# main.net
KiCad netlist of a schematic drawn in EAGLE
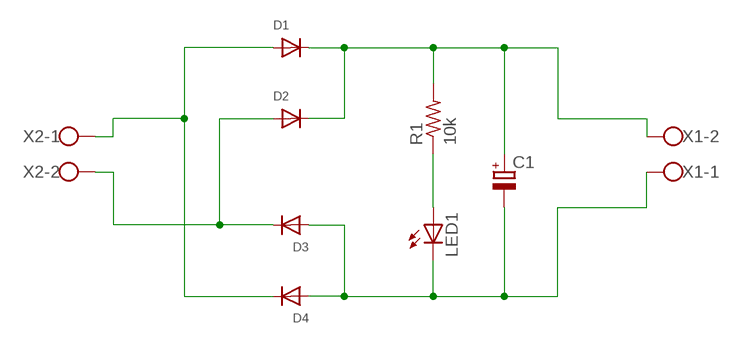
[diagram p0: schematic, sheet 1]

(export (version "E")
  (design (tool "Eeschema 10.0.6"))
  (components
    (comp (ref "C1")
      (value "C-POL_RADIAL-25MM-DIA")
      (footprint "eagle-import:CAPPRD550W110D1250H2500B")
      (libsource (lib "eagle-import") (part "C-POLRADIAL-25MM-DIA_"))
    )
    (comp (ref "D1")
      (value "DIODEDO-1N4148")
      (footprint "eagle-import:DO-1N4148")
      (libsource (lib "eagle-import") (part "DIODEDO-1N4148"))
    )
    (comp (ref "D2")
      (value "DIODEDO-1N4148")
      (footprint "eagle-import:DO-1N4148")
      (libsource (lib "eagle-import") (part "DIODEDO-1N4148"))
    )
    (comp (ref "D3")
      (value "DIODEDO-1N4148")
      (footprint "eagle-import:DO-1N4148")
      (libsource (lib "eagle-import") (part "DIODEDO-1N4148"))
    )
    (comp (ref "D4")
      (value "DIODEDO-1N4148")
      (footprint "eagle-import:DO-1N4148")
      (libsource (lib "eagle-import") (part "DIODEDO-1N4148"))
    )
    (comp (ref "LED1")
      (value "LED5MM")
      (footprint "eagle-import:LED5MM")
      (libsource (lib "eagle-import") (part "LED5MM"))
    )
    (comp (ref "R1")
      (value "10k")
      (footprint "eagle-import:0204_7")
      (libsource (lib "eagle-import") (part "R-US_0204/7"))
    )
    (comp (ref "X1")
      (value "W237-102")
      (footprint "eagle-import:W237-102")
      (fields (field (name "MPN") "237-102"))
      (libsource (lib "eagle-import") (part "W237-102"))
    )
    (comp (ref "X2")
      (value "W237-102")
      (footprint "eagle-import:W237-102")
      (fields (field (name "MPN") "237-102"))
      (libsource (lib "eagle-import") (part "W237-102"))
    )
  )
  (nets
    (net (code "1") (name "Net-(C1-+)") (class "Default")
      (node (ref "C1") (pin "1") (pinfunction "+_1") (pintype "passive"))
      (node (ref "D1") (pin "C") (pinfunction "C_C") (pintype "passive"))
      (node (ref "D2") (pin "C") (pinfunction "C_C") (pintype "passive"))
      (node (ref "R1") (pin "2") (pinfunction "2_2") (pintype "passive"))
      (node (ref "X1") (pin "2") (pinfunction "KL_2") (pintype "passive"))
    )
    (net (code "2") (name "Net-(C1--)") (class "Default")
      (node (ref "C1") (pin "2") (pinfunction "-_2") (pintype "passive"))
      (node (ref "D3") (pin "A") (pinfunction "A_A") (pintype "passive"))
      (node (ref "D4") (pin "A") (pinfunction "A_A") (pintype "passive"))
      (node (ref "LED1") (pin "K") (pinfunction "C_K") (pintype "passive"))
      (node (ref "X1") (pin "1") (pinfunction "KL_1") (pintype "passive"))
    )
    (net (code "3") (name "Net-(LED1-PadA)") (class "Default")
      (node (ref "LED1") (pin "A") (pinfunction "A_A") (pintype "passive"))
      (node (ref "R1") (pin "1") (pinfunction "1_1") (pintype "passive"))
    )
    (net (code "4") (name "Net-(X2A-KL)") (class "Default")
      (node (ref "D1") (pin "A") (pinfunction "A_A") (pintype "passive"))
      (node (ref "D4") (pin "C") (pinfunction "C_C") (pintype "passive"))
      (node (ref "X2") (pin "1") (pinfunction "KL_1") (pintype "passive"))
    )
    (net (code "5") (name "Net-(X2B-KL)") (class "Default")
      (node (ref "D2") (pin "A") (pinfunction "A_A") (pintype "passive"))
      (node (ref "D3") (pin "C") (pinfunction "C_C") (pintype "passive"))
      (node (ref "X2") (pin "2") (pinfunction "KL_2") (pintype "passive"))
    )
  )
)
